# Esquematico_sensores.net
KiCad netlist of a schematic drawn in EAGLE
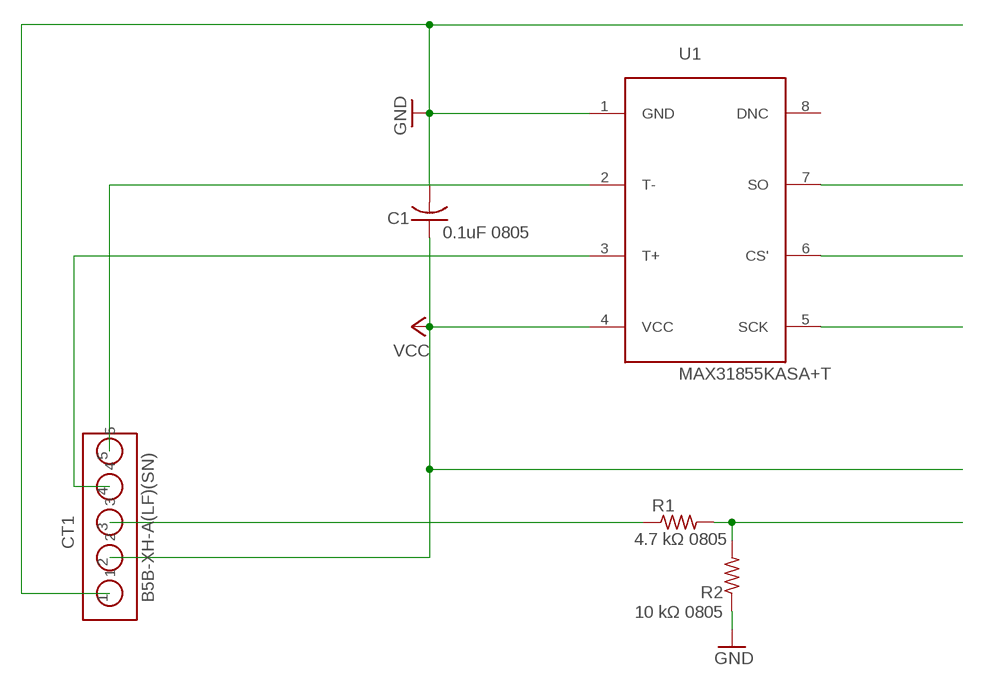
[diagram p0: schematic, sheet 1]

(export (version "E")
  (design (tool "Eeschema 10.0.6"))
  (components
    (comp (ref "C1")
      (value "0.1uF 0805")
      (footprint "eagle-import:C0805")
      (fields (field (name "PART_NO") "GCM21BR72A104KA37L"))
      (libsource (lib "eagle-import") (part "C-USC0805"))
    )
    (comp (ref "CT1")
      (value "B5B-XH-A(LF)(SN)")
      (footprint "eagle-import:5-PIN-JST")
      (libsource (lib "eagle-import") (part "B5B-XH-A(LF)(SN)"))
    )
    (comp (ref "R1")
      (value "4.7 kΩ 0805")
      (footprint "eagle-import:R0805")
      (fields (field (name "PART_NO") "RC0805FR-074K7L "))
      (libsource (lib "eagle-import") (part "R-US_R0805"))
    )
    (comp (ref "R2")
      (value "10 kΩ 0805")
      (footprint "eagle-import:R0805")
      (fields (field (name "PART_NO") "RC0805FR-0710KL"))
      (libsource (lib "eagle-import") (part "R-US_R0805"))
    )
    (comp (ref "U1")
      (value "MAX31855KASA+T")
      (footprint "eagle-import:8-SOIC")
      (libsource (lib "eagle-import") (part "MAX31855KASA+T"))
    )
  )
  (nets
    (net (code "1") (name "GND") (class "Default")
      (node (ref "C1") (pin "2") (pinfunction "2_2") (pintype "passive"))
      (node (ref "CT1") (pin "1") (pinfunction "1_1") (pintype "passive"))
      (node (ref "R2") (pin "1") (pinfunction "1_1") (pintype "passive"))
      (node (ref "U1") (pin "1") (pinfunction "GND_1") (pintype "power_in"))
    )
    (net (code "2") (name "Net-(CT1-Pad3)") (class "Default")
      (node (ref "CT1") (pin "3") (pinfunction "3_3") (pintype "passive"))
      (node (ref "R1") (pin "1") (pinfunction "1_1") (pintype "passive"))
    )
    (net (code "3") (name "Net-(R1-Pad2)") (class "Default")
      (node (ref "R1") (pin "2") (pinfunction "2_2") (pintype "passive"))
      (node (ref "R2") (pin "2") (pinfunction "2_2") (pintype "passive"))
    )
    (net (code "4") (name "Net-(U1-T+)") (class "Default")
      (node (ref "CT1") (pin "4") (pinfunction "4_4") (pintype "passive"))
      (node (ref "U1") (pin "3") (pinfunction "T+_3") (pintype "passive"))
    )
    (net (code "5") (name "Net-(U1-T-)") (class "Default")
      (node (ref "CT1") (pin "5") (pinfunction "5_5") (pintype "passive"))
      (node (ref "U1") (pin "2") (pinfunction "T-_2") (pintype "passive"))
    )
    (net (code "6") (name "VCC") (class "Default")
      (node (ref "C1") (pin "1") (pinfunction "1_1") (pintype "passive"))
      (node (ref "CT1") (pin "2") (pinfunction "2_2") (pintype "passive"))
      (node (ref "U1") (pin "4") (pinfunction "VCC_4") (pintype "power_in"))
    )
    (net (code "7") (name "unconnected-(U1-CS'-Pad6)") (class "Default")
      (node (ref "U1") (pin "6") (pinfunction "CS'_6") (pintype "input"))
    )
    (net (code "8") (name "unconnected-(U1-DNC-Pad8)") (class "Default")
      (node (ref "U1") (pin "8") (pinfunction "DNC_8") (pintype "no_connect"))
    )
    (net (code "9") (name "unconnected-(U1-SCK-Pad5)") (class "Default")
      (node (ref "U1") (pin "5") (pinfunction "SCK_5") (pintype "input"))
    )
    (net (code "10") (name "unconnected-(U1-SO-Pad7)") (class "Default")
      (node (ref "U1") (pin "7") (pinfunction "SO_7") (pintype "output"))
    )
  )
)
